# Sheet1.net
KiCad netlist of a schematic drawn in Altium Designer
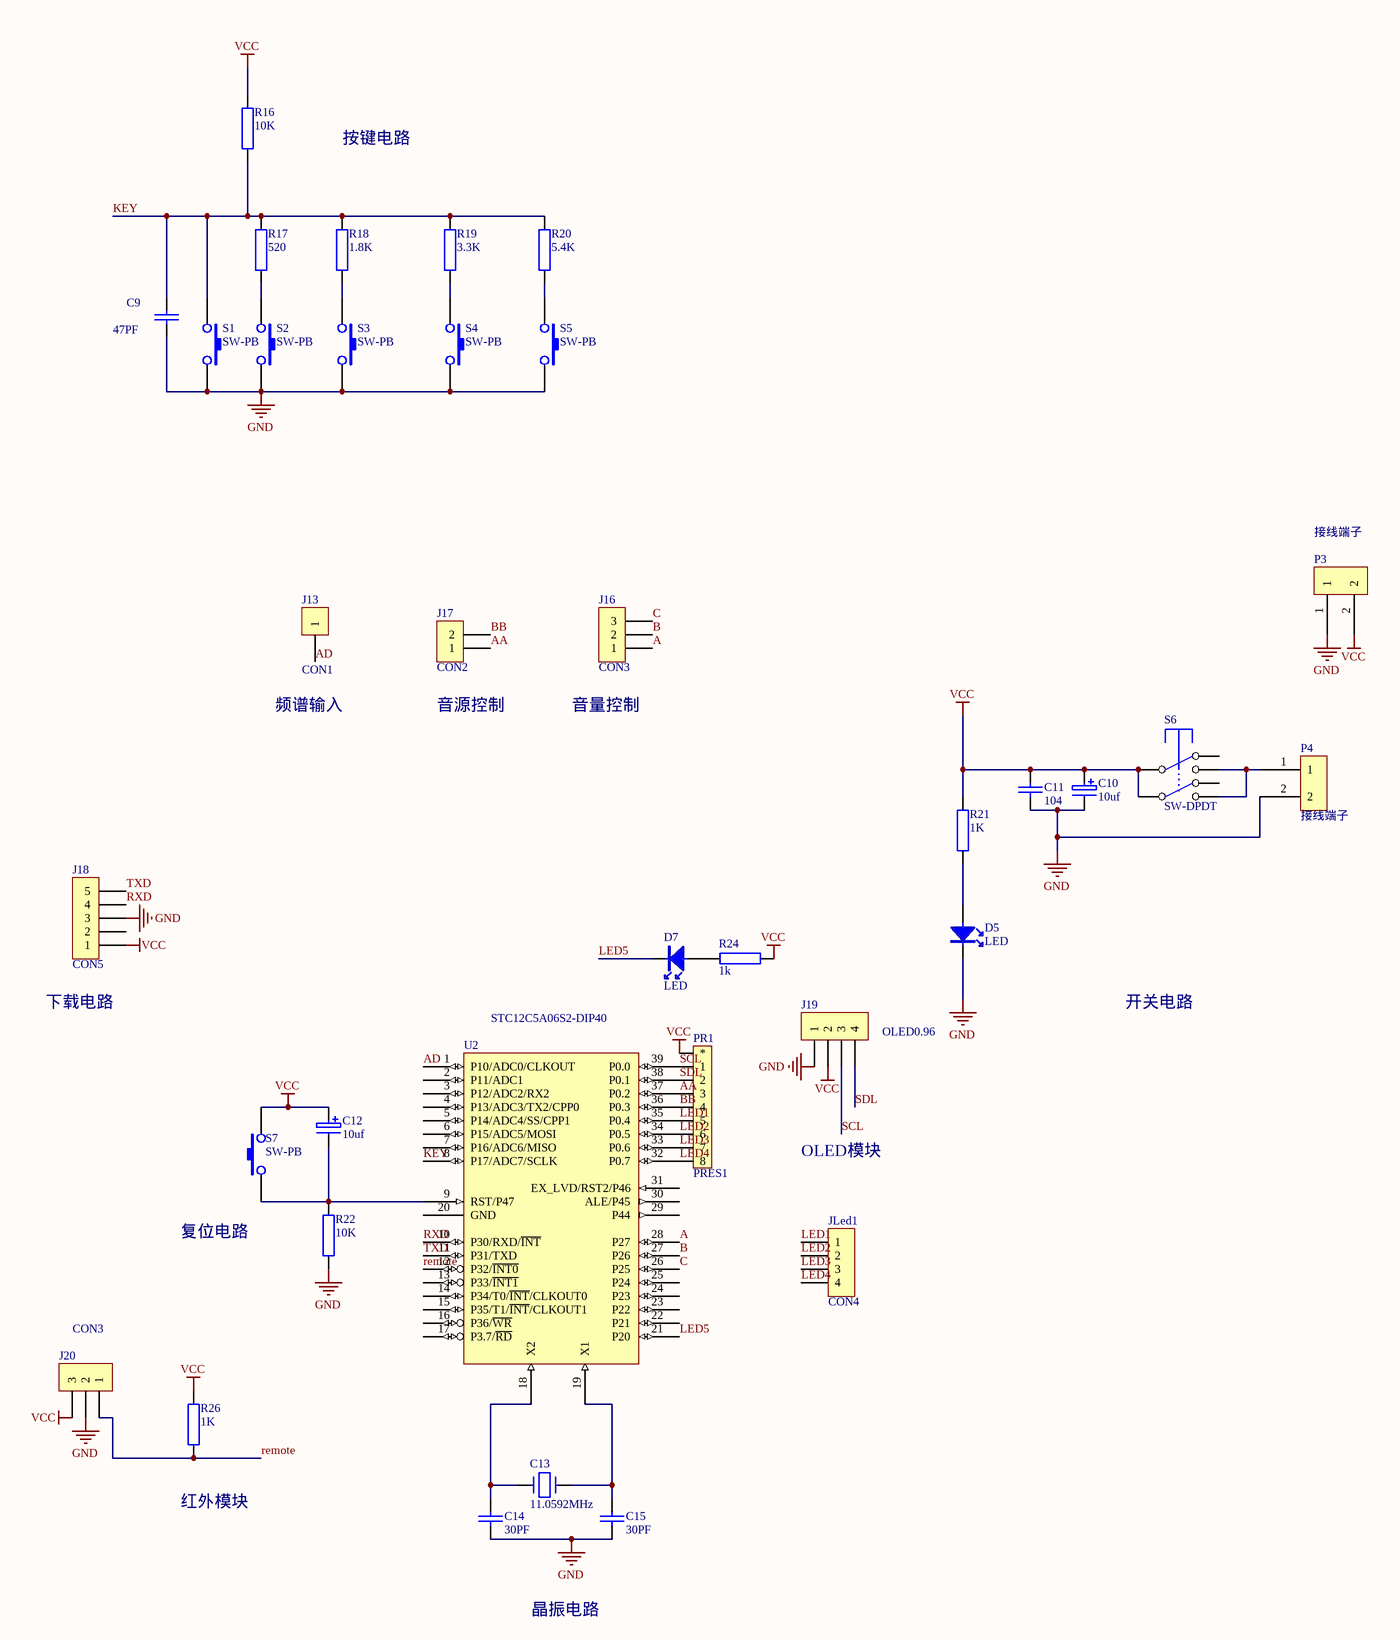
[diagram p0: Sheet1.SchDoc]

(export (version "E")
  (design (tool "Eeschema 10.0.6"))
  (components
    (comp (ref "C9") (value "47PF") (footprint "CAP2") (libsource (lib "电容") (part "CAP1")))
    (comp (ref "C10") (value "10uf") (footprint "CAO2") (libsource (lib "电容") (part "CAP3")))
    (comp (ref "C11") (value "104") (footprint "CAP2") (libsource (lib "电容") (part "CAP1")))
    (comp (ref "C12") (value "10uf") (footprint "CAO2") (libsource (lib "电容") (part "CAP3")))
    (comp (ref "C13") (value "11.0592MHz") (footprint "XTAL1") (libsource (lib "晶振") (part "CPY")))
    (comp (ref "C14") (value "30PF") (footprint "CAP2") (libsource (lib "电容") (part "CAP1")))
    (comp (ref "C15") (value "30PF") (footprint "CAP2") (libsource (lib "电容") (part "CAP1")))
    (comp (ref "D5") (value "LED") (footprint "LED2_B") (libsource (lib "二极管") (part "LED")))
    (comp (ref "D7") (value "LED") (footprint "LED2_B") (libsource (lib "二极管") (part "LED")))
    (comp (ref "J13")
      (value "CON1")
      (footprint "SIP-1")
      (description "Connector")
      (libsource (lib "排针") (part "CON1"))
    )
    (comp (ref "J16")
      (value "CON3")
      (footprint "sip-3")
      (description "Connector")
      (libsource (lib "排针") (part "CON3"))
    )
    (comp (ref "J17")
      (value "CON2")
      (footprint "sip-2")
      (description "Connector")
      (libsource (lib "排针") (part "CON2"))
    )
    (comp (ref "J18")
      (value "CON5")
      (footprint "sip-5")
      (description "Connector")
      (libsource (lib "排针") (part "CON5"))
    )
    (comp (ref "J19")
      (value "OLED0.96")
      (footprint "sip-4")
      (description "Connector")
      (libsource (lib "排针") (part "CON4"))
    )
    (comp (ref "J20")
      (value "CON3")
      (footprint "sip-3")
      (description "Connector")
      (libsource (lib "") (part "CON3_1"))
    )
    (comp (ref "JLed1")
      (value "CON4")
      (footprint "sip-4")
      (description "Connector")
      (libsource (lib "") (part "CON4_1"))
    )
    (comp (ref "P3") (value "接线端子") (footprint "音频功放自画库:接线端子") (libsource (lib "") (part "接线端子_1")))
    (comp (ref "P4") (value "接线端子") (footprint "音频功放自画库:接线端子") (libsource (lib "音频功放自画库") (part "接线端子")))
    (comp (ref "PR1") (value "PRES1") (footprint "RP1") (libsource (lib "电阻") (part "PRES1")))
    (comp (ref "R16")
      (value "10K")
      (footprint "AXIAL0.4")
      (description "电阻")
      (libsource (lib "电阻") (part "RES"))
    )
    (comp (ref "R17")
      (value "520")
      (footprint "AXIAL0.4")
      (description "电阻")
      (libsource (lib "电阻") (part "RES"))
    )
    (comp (ref "R18")
      (value "1.8K")
      (footprint "AXIAL0.4")
      (description "电阻")
      (libsource (lib "电阻") (part "RES"))
    )
    (comp (ref "R19")
      (value "3.3K")
      (footprint "AXIAL0.4")
      (description "电阻")
      (libsource (lib "电阻") (part "RES"))
    )
    (comp (ref "R20")
      (value "5.4K")
      (footprint "AXIAL0.4")
      (description "电阻")
      (libsource (lib "电阻") (part "RES"))
    )
    (comp (ref "R21")
      (value "1K")
      (footprint "AXIAL0.4")
      (description "电阻")
      (libsource (lib "电阻") (part "RES"))
    )
    (comp (ref "R22")
      (value "10K")
      (footprint "AXIAL0.4")
      (description "电阻")
      (libsource (lib "电阻") (part "RES"))
    )
    (comp (ref "R24")
      (value "1k")
      (footprint "AXIAL0.4")
      (description "电阻")
      (libsource (lib "电阻") (part "RES"))
    )
    (comp (ref "R26")
      (value "1K")
      (footprint "AXIAL0.4")
      (description "电阻")
      (libsource (lib "电阻") (part "RES"))
    )
    (comp (ref "S1") (value "SW-PB") (footprint "SW6*6") (libsource (lib "开关") (part "SW-PB")))
    (comp (ref "S2") (value "SW-PB") (footprint "SW6*6") (libsource (lib "开关") (part "SW-PB")))
    (comp (ref "S3") (value "SW-PB") (footprint "SW6*6") (libsource (lib "开关") (part "SW-PB")))
    (comp (ref "S4") (value "SW-PB") (footprint "SW6*6") (libsource (lib "开关") (part "SW-PB")))
    (comp (ref "S5") (value "SW-PB") (footprint "SW6*6") (libsource (lib "开关") (part "SW-PB")))
    (comp (ref "S6") (value "SW-DPDT") (footprint "SWH8*8") (libsource (lib "开关") (part "SW-DPDT")))
    (comp (ref "S7") (value "SW-PB") (footprint "SW6*6") (libsource (lib "开关") (part "SW-PB")))
    (comp (ref "U2")
      (value "STC12C5A06S2-DIP40")
      (footprint "DIP-40")
      (libsource (lib "单片机") (part "STC12C5A06S2-DIP40"))
    )
  )
  (nets
    (net (code "1") (name "/A") (class "Default")
      (node (ref "J16") (pin "1") (pinfunction "1_1") (pintype "passive"))
      (node (ref "U2") (pin "28") (pinfunction "P27_28") (pintype "bidirectional"))
    )
    (net (code "2") (name "/AA") (class "Default")
      (node (ref "J17") (pin "1") (pinfunction "1_1") (pintype "passive"))
      (node (ref "PR1") (pin "4") (pinfunction "3_4") (pintype "passive"))
      (node (ref "U2") (pin "37") (pinfunction "P0.2_37") (pintype "bidirectional"))
    )
    (net (code "3") (name "/AD") (class "Default")
      (node (ref "J13") (pin "1") (pinfunction "1_1") (pintype "passive"))
      (node (ref "U2") (pin "1") (pinfunction "P10/ADC0/CLKOUT_1") (pintype "bidirectional"))
    )
    (net (code "4") (name "/B") (class "Default")
      (node (ref "J16") (pin "2") (pinfunction "2_2") (pintype "passive"))
      (node (ref "U2") (pin "27") (pinfunction "P26_27") (pintype "bidirectional"))
    )
    (net (code "5") (name "/BB") (class "Default")
      (node (ref "J17") (pin "2") (pinfunction "2_2") (pintype "passive"))
      (node (ref "PR1") (pin "5") (pinfunction "4_5") (pintype "passive"))
      (node (ref "U2") (pin "36") (pinfunction "P0.3_36") (pintype "bidirectional"))
    )
    (net (code "6") (name "/C") (class "Default")
      (node (ref "J16") (pin "3") (pinfunction "3_3") (pintype "passive"))
      (node (ref "U2") (pin "26") (pinfunction "P25_26") (pintype "bidirectional"))
    )
    (net (code "7") (name "/KEY") (class "Default")
      (node (ref "C9") (pin "1") (pinfunction "1_1") (pintype "passive"))
      (node (ref "R16") (pin "1") (pinfunction "1_1") (pintype "passive"))
      (node (ref "R17") (pin "2") (pinfunction "2_2") (pintype "passive"))
      (node (ref "R18") (pin "2") (pinfunction "2_2") (pintype "passive"))
      (node (ref "R19") (pin "2") (pinfunction "2_2") (pintype "passive"))
      (node (ref "R20") (pin "2") (pinfunction "2_2") (pintype "passive"))
      (node (ref "S1") (pin "1") (pinfunction "1_1") (pintype "passive"))
      (node (ref "U2") (pin "8") (pinfunction "P17/ADC7/SCLK_8") (pintype "bidirectional"))
    )
    (net (code "8") (name "/LED1") (class "Default")
      (node (ref "JLed1") (pin "1") (pinfunction "1_1") (pintype "passive"))
      (node (ref "PR1") (pin "6") (pinfunction "5_6") (pintype "passive"))
      (node (ref "U2") (pin "35") (pinfunction "P0.4_35") (pintype "bidirectional"))
    )
    (net (code "9") (name "/LED2") (class "Default")
      (node (ref "JLed1") (pin "2") (pinfunction "2_2") (pintype "passive"))
      (node (ref "PR1") (pin "7") (pinfunction "6_7") (pintype "passive"))
      (node (ref "U2") (pin "34") (pinfunction "P0.5_34") (pintype "bidirectional"))
    )
    (net (code "10") (name "/LED3") (class "Default")
      (node (ref "JLed1") (pin "3") (pinfunction "3_3") (pintype "passive"))
      (node (ref "PR1") (pin "8") (pinfunction "7_8") (pintype "passive"))
      (node (ref "U2") (pin "33") (pinfunction "P0.6_33") (pintype "bidirectional"))
    )
    (net (code "11") (name "/LED4") (class "Default")
      (node (ref "JLed1") (pin "4") (pinfunction "4_4") (pintype "passive"))
      (node (ref "PR1") (pin "9") (pinfunction "8_9") (pintype "passive"))
      (node (ref "U2") (pin "32") (pinfunction "P0.7_32") (pintype "bidirectional"))
    )
    (net (code "12") (name "/LED5") (class "Default")
      (node (ref "D7") (pin "2") (pinfunction "2_2") (pintype "passive"))
      (node (ref "U2") (pin "21") (pinfunction "P20_21") (pintype "bidirectional"))
    )
    (net (code "13") (name "/RXD") (class "Default")
      (node (ref "J18") (pin "4") (pinfunction "4_4") (pintype "passive"))
      (node (ref "U2") (pin "10") (pinfunction "P30/RXD/~{INT}_10") (pintype "bidirectional"))
    )
    (net (code "14") (name "/SCL") (class "Default")
      (node (ref "J19") (pin "3") (pinfunction "3_3") (pintype "passive"))
      (node (ref "PR1") (pin "2") (pinfunction "1_2") (pintype "passive"))
      (node (ref "U2") (pin "39") (pinfunction "P0.0_39") (pintype "bidirectional"))
    )
    (net (code "15") (name "/SDL") (class "Default")
      (node (ref "J19") (pin "4") (pinfunction "4_4") (pintype "passive"))
      (node (ref "PR1") (pin "3") (pinfunction "2_3") (pintype "passive"))
      (node (ref "U2") (pin "38") (pinfunction "P0.1_38") (pintype "bidirectional"))
    )
    (net (code "16") (name "/TXD") (class "Default")
      (node (ref "J18") (pin "5") (pinfunction "5_5") (pintype "passive"))
      (node (ref "U2") (pin "11") (pinfunction "P31/TXD_11") (pintype "bidirectional"))
    )
    (net (code "17") (name "/remote") (class "Default")
      (node (ref "J20") (pin "1") (pinfunction "1_1") (pintype "passive"))
      (node (ref "R26") (pin "1") (pinfunction "1_1") (pintype "passive"))
      (node (ref "U2") (pin "12") (pinfunction "P32/~{INT0}_12") (pintype "bidirectional"))
    )
    (net (code "18") (name "GND") (class "Default")
      (node (ref "C10") (pin "2") (pintype "passive"))
      (node (ref "C11") (pin "2") (pinfunction "2_2") (pintype "passive"))
      (node (ref "C14") (pin "2") (pinfunction "2_2") (pintype "passive"))
      (node (ref "C15") (pin "2") (pinfunction "2_2") (pintype "passive"))
      (node (ref "C9") (pin "2") (pinfunction "2_2") (pintype "passive"))
      (node (ref "D5") (pin "2") (pinfunction "2_2") (pintype "passive"))
      (node (ref "J18") (pin "3") (pinfunction "3_3") (pintype "passive"))
      (node (ref "J19") (pin "1") (pinfunction "1_1") (pintype "passive"))
      (node (ref "J20") (pin "2") (pinfunction "2_2") (pintype "passive"))
      (node (ref "P3") (pin "1") (pinfunction "1_1") (pintype "passive"))
      (node (ref "P4") (pin "2") (pinfunction "2_2") (pintype "passive"))
      (node (ref "R22") (pin "1") (pinfunction "1_1") (pintype "passive"))
      (node (ref "S1") (pin "2") (pinfunction "2_2") (pintype "passive"))
      (node (ref "S2") (pin "2") (pinfunction "2_2") (pintype "passive"))
      (node (ref "S3") (pin "2") (pinfunction "2_2") (pintype "passive"))
      (node (ref "S4") (pin "2") (pinfunction "2_2") (pintype "passive"))
      (node (ref "S5") (pin "2") (pinfunction "2_2") (pintype "passive"))
    )
    (net (code "19") (name "Net-(D5-Pad1)") (class "Default")
      (node (ref "D5") (pin "1") (pinfunction "1_1") (pintype "passive"))
      (node (ref "R21") (pin "1") (pinfunction "1_1") (pintype "passive"))
    )
    (net (code "20") (name "Net-(D7-Pad1)") (class "Default")
      (node (ref "D7") (pin "1") (pinfunction "1_1") (pintype "passive"))
      (node (ref "R24") (pin "2") (pinfunction "2_2") (pintype "passive"))
    )
    (net (code "21") (name "Net-(P4-Pad1)") (class "Default")
      (node (ref "P4") (pin "1") (pinfunction "1_1") (pintype "passive"))
      (node (ref "S6") (pin "3") (pinfunction "3_3") (pintype "passive"))
      (node (ref "S6") (pin "4") (pinfunction "4_4") (pintype "passive"))
    )
    (net (code "22") (name "Net-(R17-Pad1)") (class "Default")
      (node (ref "R17") (pin "1") (pinfunction "1_1") (pintype "passive"))
      (node (ref "S2") (pin "1") (pinfunction "1_1") (pintype "passive"))
    )
    (net (code "23") (name "Net-(R18-Pad1)") (class "Default")
      (node (ref "R18") (pin "1") (pinfunction "1_1") (pintype "passive"))
      (node (ref "S3") (pin "1") (pinfunction "1_1") (pintype "passive"))
    )
    (net (code "24") (name "Net-(R19-Pad1)") (class "Default")
      (node (ref "R19") (pin "1") (pinfunction "1_1") (pintype "passive"))
      (node (ref "S4") (pin "1") (pinfunction "1_1") (pintype "passive"))
    )
    (net (code "25") (name "Net-(R20-Pad1)") (class "Default")
      (node (ref "R20") (pin "1") (pinfunction "1_1") (pintype "passive"))
      (node (ref "S5") (pin "1") (pinfunction "1_1") (pintype "passive"))
    )
    (net (code "26") (name "Net-(U2-RST{slash}P47)") (class "Default")
      (node (ref "C12") (pin "2") (pintype "passive"))
      (node (ref "R22") (pin "2") (pinfunction "2_2") (pintype "passive"))
      (node (ref "S7") (pin "1") (pinfunction "1_1") (pintype "passive"))
      (node (ref "U2") (pin "9") (pinfunction "RST/P47_9") (pintype "input"))
    )
    (net (code "27") (name "Net-(U2-X1)") (class "Default")
      (node (ref "C13") (pin "2") (pintype "passive"))
      (node (ref "C15") (pin "1") (pinfunction "1_1") (pintype "passive"))
      (node (ref "U2") (pin "19") (pinfunction "X1_19") (pintype "input"))
    )
    (net (code "28") (name "Net-(U2-X2)") (class "Default")
      (node (ref "C13") (pin "1") (pintype "passive"))
      (node (ref "C14") (pin "1") (pinfunction "1_1") (pintype "passive"))
      (node (ref "U2") (pin "18") (pinfunction "X2_18") (pintype "input"))
    )
    (net (code "29") (name "VCC") (class "Default")
      (node (ref "C10") (pin "1") (pintype "passive"))
      (node (ref "C11") (pin "1") (pinfunction "1_1") (pintype "passive"))
      (node (ref "C12") (pin "1") (pintype "passive"))
      (node (ref "J18") (pin "1") (pinfunction "1_1") (pintype "passive"))
      (node (ref "J19") (pin "2") (pinfunction "2_2") (pintype "passive"))
      (node (ref "J20") (pin "3") (pinfunction "3_3") (pintype "passive"))
      (node (ref "P3") (pin "2") (pinfunction "2_2") (pintype "passive"))
      (node (ref "PR1") (pin "1") (pinfunction "*_1") (pintype "passive"))
      (node (ref "R16") (pin "2") (pinfunction "2_2") (pintype "passive"))
      (node (ref "R21") (pin "2") (pinfunction "2_2") (pintype "passive"))
      (node (ref "R24") (pin "1") (pinfunction "1_1") (pintype "passive"))
      (node (ref "R26") (pin "2") (pinfunction "2_2") (pintype "passive"))
      (node (ref "S6") (pin "2") (pinfunction "2_2") (pintype "passive"))
      (node (ref "S6") (pin "5") (pinfunction "5_5") (pintype "passive"))
      (node (ref "S7") (pin "2") (pinfunction "2_2") (pintype "passive"))
      (node (ref "U2") (pin "40") (pinfunction "VCC_40") (pintype "power_in"))
    )
    (net (code "30") (name "unconnected-(J18-Pad2)") (class "Default")
      (node (ref "J18") (pin "2") (pinfunction "2_2") (pintype "passive"))
    )
    (net (code "31") (name "unconnected-(S6-Pad1)") (class "Default")
      (node (ref "S6") (pin "1") (pinfunction "1_1") (pintype "passive"))
    )
    (net (code "32") (name "unconnected-(S6-Pad6)") (class "Default")
      (node (ref "S6") (pin "6") (pinfunction "6_6") (pintype "passive"))
    )
    (net (code "33") (name "unconnected-(U2-ALE{slash}P45-Pad30)") (class "Default")
      (node (ref "U2") (pin "30") (pinfunction "ALE/P45_30") (pintype "output"))
    )
    (net (code "34") (name "unconnected-(U2-EX_LVD{slash}RST2{slash}P46-Pad31)") (class "Default")
      (node (ref "U2") (pin "31") (pinfunction "EX_LVD/RST2/P46_31") (pintype "input"))
    )
    (net (code "35") (name "unconnected-(U2-GND-Pad20)") (class "Default")
      (node (ref "U2") (pin "20") (pinfunction "GND_20") (pintype "power_in"))
    )
    (net (code "36") (name "unconnected-(U2-P3.7{slash}~{RD}-Pad17)") (class "Default")
      (node (ref "U2") (pin "17") (pinfunction "P3.7/~{RD}_17") (pintype "bidirectional"))
    )
    (net (code "37") (name "unconnected-(U2-P11{slash}ADC1-Pad2)") (class "Default")
      (node (ref "U2") (pin "2") (pinfunction "P11/ADC1_2") (pintype "bidirectional"))
    )
    (net (code "38") (name "unconnected-(U2-P12{slash}ADC2{slash}RX2-Pad3)") (class "Default")
      (node (ref "U2") (pin "3") (pinfunction "P12/ADC2/RX2_3") (pintype "bidirectional"))
    )
    (net (code "39") (name "unconnected-(U2-P13{slash}ADC3{slash}TX2{slash}CPP0-Pad4)") (class "Default")
      (node (ref "U2") (pin "4") (pinfunction "P13/ADC3/TX2/CPP0_4") (pintype "bidirectional"))
    )
    (net (code "40") (name "unconnected-(U2-P14{slash}ADC4{slash}SS{slash}CPP1-Pad5)") (class "Default")
      (node (ref "U2") (pin "5") (pinfunction "P14/ADC4/SS/CPP1_5") (pintype "bidirectional"))
    )
    (net (code "41") (name "unconnected-(U2-P15{slash}ADC5{slash}MOSI-Pad6)") (class "Default")
      (node (ref "U2") (pin "6") (pinfunction "P15/ADC5/MOSI_6") (pintype "bidirectional"))
    )
    (net (code "42") (name "unconnected-(U2-P16{slash}ADC6{slash}MISO-Pad7)") (class "Default")
      (node (ref "U2") (pin "7") (pinfunction "P16/ADC6/MISO_7") (pintype "bidirectional"))
    )
    (net (code "43") (name "unconnected-(U2-P21-Pad22)") (class "Default")
      (node (ref "U2") (pin "22") (pinfunction "P21_22") (pintype "bidirectional"))
    )
    (net (code "44") (name "unconnected-(U2-P22-Pad23)") (class "Default")
      (node (ref "U2") (pin "23") (pinfunction "P22_23") (pintype "bidirectional"))
    )
    (net (code "45") (name "unconnected-(U2-P23-Pad24)") (class "Default")
      (node (ref "U2") (pin "24") (pinfunction "P23_24") (pintype "bidirectional"))
    )
    (net (code "46") (name "unconnected-(U2-P24-Pad25)") (class "Default")
      (node (ref "U2") (pin "25") (pinfunction "P24_25") (pintype "bidirectional"))
    )
    (net (code "47") (name "unconnected-(U2-P33{slash}~{INT1}-Pad13)") (class "Default")
      (node (ref "U2") (pin "13") (pinfunction "P33/~{INT1}_13") (pintype "bidirectional"))
    )
    (net (code "48") (name "unconnected-(U2-P34{slash}T0{slash}~{INT}{slash}CLKOUT0-Pad14)") (class "Default")
      (node (ref "U2") (pin "14") (pinfunction "P34/T0/~{INT}/CLKOUT0_14") (pintype "bidirectional"))
    )
    (net (code "49") (name "unconnected-(U2-P35{slash}T1{slash}~{INT}{slash}CLKOUT1-Pad15)") (class "Default")
      (node (ref "U2") (pin "15") (pinfunction "P35/T1/~{INT}/CLKOUT1_15") (pintype "bidirectional"))
    )
    (net (code "50") (name "unconnected-(U2-P36{slash}~{WR}-Pad16)") (class "Default")
      (node (ref "U2") (pin "16") (pinfunction "P36/~{WR}_16") (pintype "bidirectional"))
    )
    (net (code "51") (name "unconnected-(U2-P44-Pad29)") (class "Default")
      (node (ref "U2") (pin "29") (pinfunction "P44_29") (pintype "output"))
    )
  )
)
